# 8stepsV2.net
KiCad netlist of a schematic drawn in EAGLE
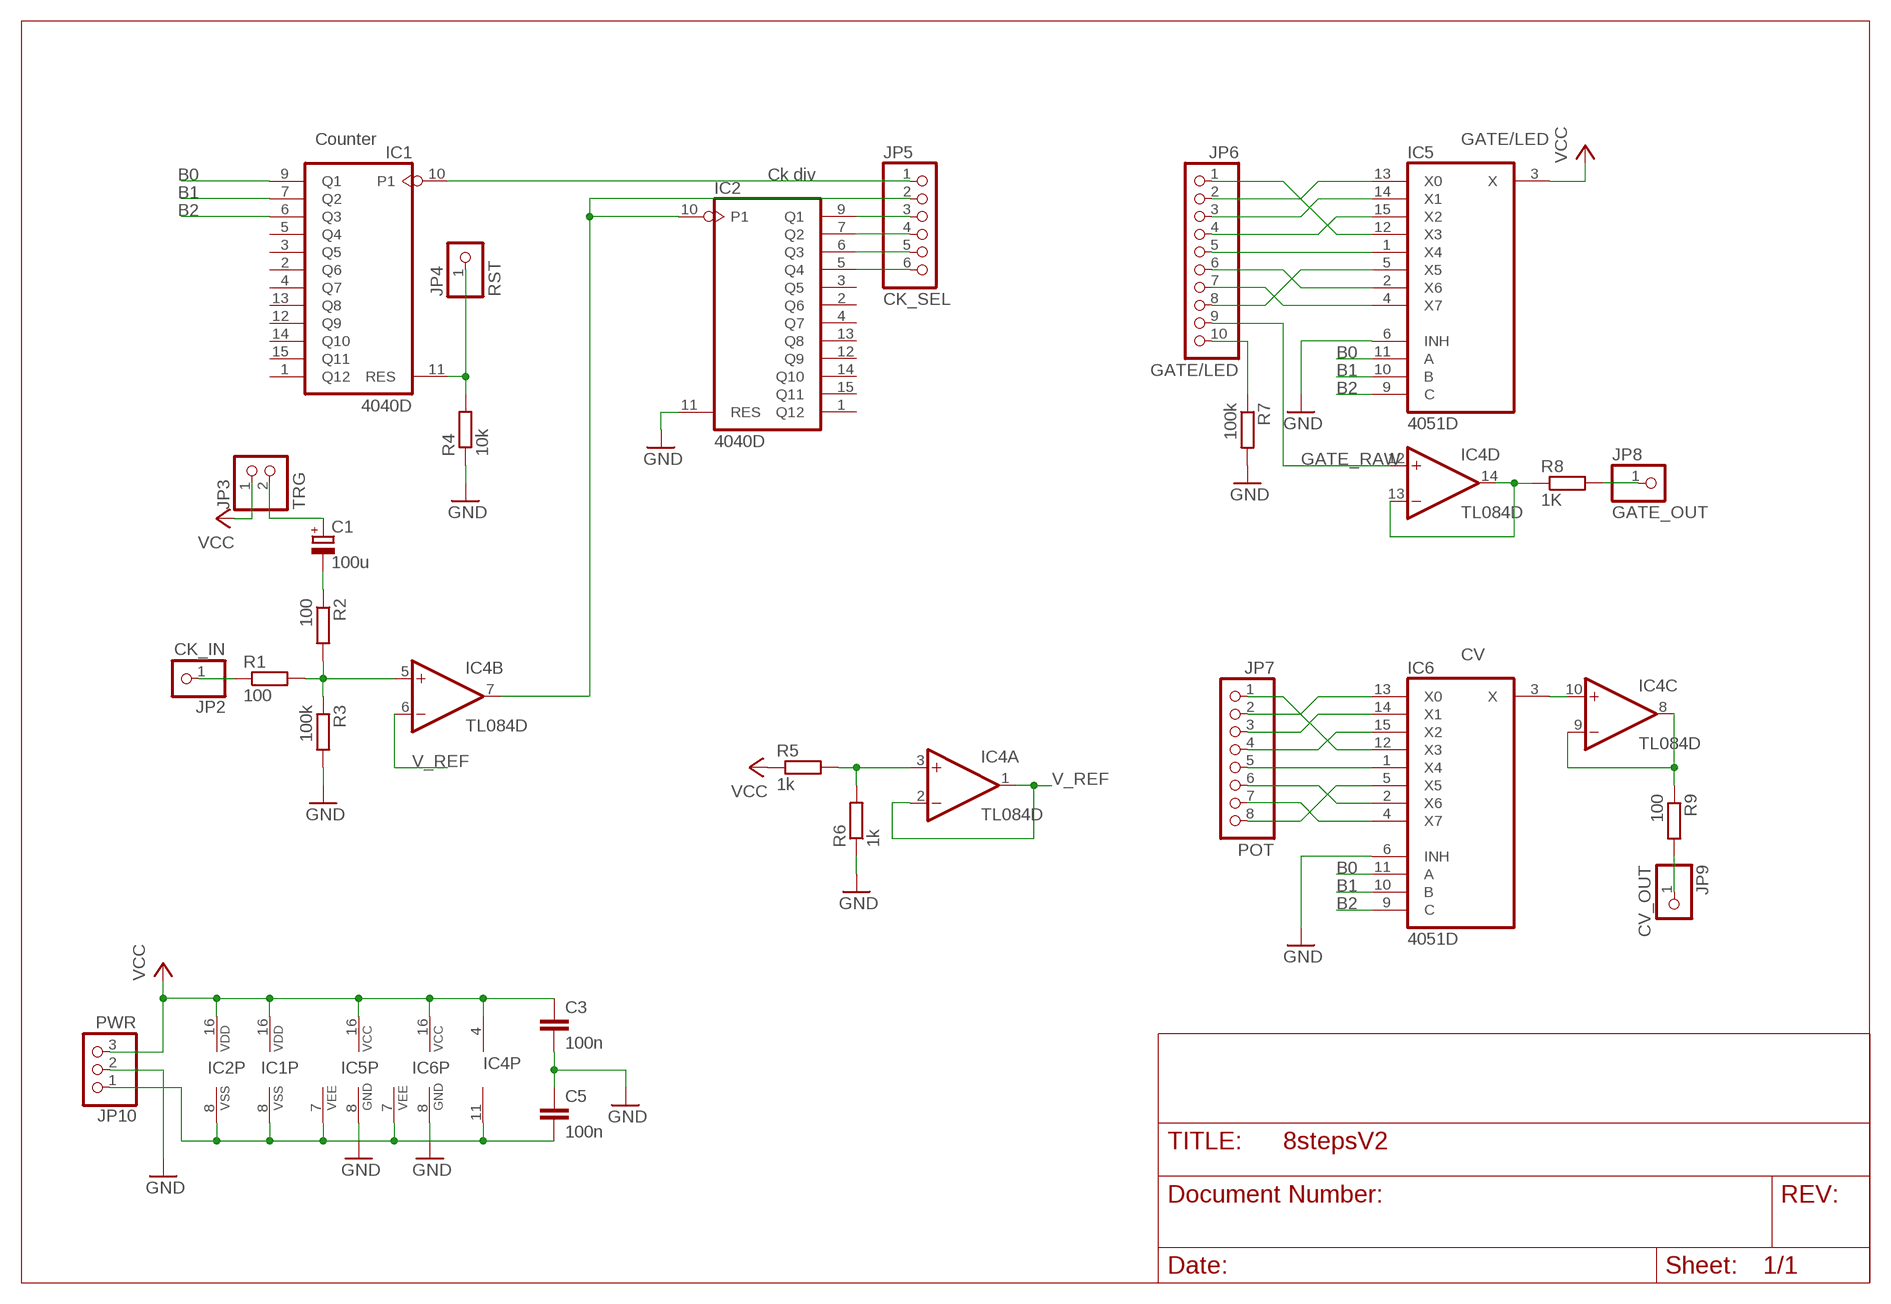
[diagram p0: schematic, sheet 1]

(export (version "E")
  (design (tool "Eeschema 10.0.6"))
  (components
    (comp (ref "C1")
      (value "100u")
      (footprint "eagle-import:E2,5-7")
      (libsource (lib "eagle-import") (part "CPOL-EUE2.5-7"))
    )
    (comp (ref "C3")
      (value "100n")
      (footprint "eagle-import:C025-024X044")
      (libsource (lib "eagle-import") (part "C-EU025-024X044"))
    )
    (comp (ref "C5")
      (value "100n")
      (footprint "eagle-import:C025-024X044")
      (libsource (lib "eagle-import") (part "C-EU025-024X044"))
    )
    (comp (ref "IC1")
      (value "4040D")
      (footprint "eagle-import:SO16")
      (libsource (lib "eagle-import") (part "4040D"))
    )
    (comp (ref "IC2")
      (value "4040D")
      (footprint "eagle-import:SO16")
      (libsource (lib "eagle-import") (part "4040D"))
    )
    (comp (ref "IC4")
      (value "TL084D")
      (footprint "eagle-import:SO14")
      (libsource (lib "eagle-import") (part "TL084D"))
    )
    (comp (ref "IC5")
      (value "4051D")
      (footprint "eagle-import:SO16")
      (libsource (lib "eagle-import") (part "4051D"))
    )
    (comp (ref "IC6")
      (value "4051D")
      (footprint "eagle-import:SO16")
      (libsource (lib "eagle-import") (part "4051D"))
    )
    (comp (ref "JP2")
      (value "CK_IN")
      (footprint "eagle-import:1X01")
      (libsource (lib "eagle-import") (part "PINHD-1X1"))
    )
    (comp (ref "JP3")
      (value "TRG")
      (footprint "eagle-import:1X02")
      (libsource (lib "eagle-import") (part "PINHD-1X2"))
    )
    (comp (ref "JP4")
      (value "RST")
      (footprint "eagle-import:1X01")
      (libsource (lib "eagle-import") (part "PINHD-1X1"))
    )
    (comp (ref "JP5")
      (value "CK_SEL")
      (footprint "eagle-import:1X06")
      (libsource (lib "eagle-import") (part "PINHD-1X6"))
    )
    (comp (ref "JP6")
      (value "GATE/LED")
      (footprint "eagle-import:1X10")
      (libsource (lib "eagle-import") (part "PINHD-1X10"))
    )
    (comp (ref "JP7")
      (value "POT")
      (footprint "eagle-import:1X08")
      (libsource (lib "eagle-import") (part "PINHD-1X8"))
    )
    (comp (ref "JP8")
      (value "GATE_OUT")
      (footprint "eagle-import:1X01")
      (libsource (lib "eagle-import") (part "PINHD-1X1"))
    )
    (comp (ref "JP9")
      (value "CV_OUT")
      (footprint "eagle-import:1X01")
      (libsource (lib "eagle-import") (part "PINHD-1X1"))
    )
    (comp (ref "JP10")
      (value "PWR")
      (footprint "eagle-import:1X03")
      (libsource (lib "eagle-import") (part "PINHD-1X3"))
    )
    (comp (ref "R1")
      (value "100")
      (footprint "eagle-import:R0805")
      (libsource (lib "eagle-import") (part "R-EU_R0805"))
    )
    (comp (ref "R2")
      (value "100")
      (footprint "eagle-import:R0805")
      (libsource (lib "eagle-import") (part "R-EU_R0805"))
    )
    (comp (ref "R3")
      (value "100k")
      (footprint "eagle-import:R0805")
      (libsource (lib "eagle-import") (part "R-EU_R0805"))
    )
    (comp (ref "R4")
      (value "10k")
      (footprint "eagle-import:R0805")
      (libsource (lib "eagle-import") (part "R-EU_R0805"))
    )
    (comp (ref "R5")
      (value "1k")
      (footprint "eagle-import:R0805")
      (libsource (lib "eagle-import") (part "R-EU_R0805"))
    )
    (comp (ref "R6")
      (value "1k")
      (footprint "eagle-import:R0805")
      (libsource (lib "eagle-import") (part "R-EU_R0805"))
    )
    (comp (ref "R7")
      (value "100k")
      (footprint "eagle-import:R0805")
      (libsource (lib "eagle-import") (part "R-EU_R0805"))
    )
    (comp (ref "R8")
      (value "1K")
      (footprint "eagle-import:R0805")
      (libsource (lib "eagle-import") (part "R-EU_R0805"))
    )
    (comp (ref "R9")
      (value "100")
      (footprint "eagle-import:R0805")
      (libsource (lib "eagle-import") (part "R-EU_R0805"))
    )
  )
  (nets
    (net (code "1") (name "/B0") (class "Default")
      (node (ref "IC1") (pin "9") (pinfunction "Q1_9") (pintype "output"))
      (node (ref "IC5") (pin "11") (pinfunction "A_11") (pintype "input"))
      (node (ref "IC6") (pin "11") (pinfunction "A_11") (pintype "input"))
    )
    (net (code "2") (name "/B1") (class "Default")
      (node (ref "IC1") (pin "7") (pinfunction "Q2_7") (pintype "output"))
      (node (ref "IC5") (pin "10") (pinfunction "B_10") (pintype "input"))
      (node (ref "IC6") (pin "10") (pinfunction "B_10") (pintype "input"))
    )
    (net (code "3") (name "/B2") (class "Default")
      (node (ref "IC1") (pin "6") (pinfunction "Q3_6") (pintype "output"))
      (node (ref "IC5") (pin "9") (pinfunction "C_9") (pintype "input"))
      (node (ref "IC6") (pin "9") (pinfunction "C_9") (pintype "input"))
    )
    (net (code "4") (name "/GATE_RAW") (class "Default")
      (node (ref "IC4") (pin "12") (pinfunction "+IN_12") (pintype "input"))
      (node (ref "JP6") (pin "9") (pinfunction "9_9") (pintype "passive"))
    )
    (net (code "5") (name "/V_REF") (class "Default")
      (node (ref "IC4") (pin "1") (pinfunction "OUT_1") (pintype "output"))
      (node (ref "IC4") (pin "2") (pinfunction "-IN_2") (pintype "input"))
      (node (ref "IC4") (pin "6") (pinfunction "-IN_6") (pintype "input"))
    )
    (net (code "6") (name "GND") (class "Default")
      (node (ref "C3") (pin "2") (pinfunction "2_2") (pintype "passive"))
      (node (ref "C5") (pin "1") (pinfunction "1_1") (pintype "passive"))
      (node (ref "IC2") (pin "11") (pinfunction "RES_11") (pintype "input"))
      (node (ref "IC5") (pin "6") (pinfunction "INH_6") (pintype "input"))
      (node (ref "IC5") (pin "8") (pinfunction "GND_8") (pintype "power_in"))
      (node (ref "IC6") (pin "6") (pinfunction "INH_6") (pintype "input"))
      (node (ref "IC6") (pin "8") (pinfunction "GND_8") (pintype "power_in"))
      (node (ref "JP10") (pin "2") (pinfunction "2_2") (pintype "passive"))
      (node (ref "R3") (pin "2") (pinfunction "2_2") (pintype "passive"))
      (node (ref "R4") (pin "1") (pinfunction "1_1") (pintype "passive"))
      (node (ref "R6") (pin "1") (pinfunction "1_1") (pintype "passive"))
      (node (ref "R7") (pin "2") (pinfunction "2_2") (pintype "passive"))
    )
    (net (code "7") (name "Net-(C1-Pad+)") (class "Default")
      (node (ref "C1") (pin "+") (pinfunction "+_+") (pintype "passive"))
      (node (ref "JP3") (pin "2") (pinfunction "2_2") (pintype "passive"))
    )
    (net (code "8") (name "Net-(C1-Pad-)") (class "Default")
      (node (ref "C1") (pin "-") (pinfunction "-_-") (pintype "passive"))
      (node (ref "R2") (pin "1") (pinfunction "1_1") (pintype "passive"))
    )
    (net (code "9") (name "Net-(IC1A-P1)") (class "Default")
      (node (ref "IC1") (pin "10") (pinfunction "P1_10") (pintype "input"))
      (node (ref "JP5") (pin "1") (pinfunction "1_1") (pintype "passive"))
    )
    (net (code "10") (name "Net-(IC1A-RES)") (class "Default")
      (node (ref "IC1") (pin "11") (pinfunction "RES_11") (pintype "input"))
      (node (ref "JP4") (pin "1") (pinfunction "1_1") (pintype "passive"))
      (node (ref "R4") (pin "2") (pinfunction "2_2") (pintype "passive"))
    )
    (net (code "11") (name "Net-(IC1B-VSS)") (class "Default")
      (node (ref "C5") (pin "2") (pinfunction "2_2") (pintype "passive"))
      (node (ref "IC1") (pin "8") (pinfunction "VSS_8") (pintype "power_in"))
      (node (ref "IC2") (pin "8") (pinfunction "VSS_8") (pintype "power_in"))
      (node (ref "IC4") (pin "11") (pinfunction "V-_11") (pintype "power_in"))
      (node (ref "IC5") (pin "7") (pinfunction "VEE_7") (pintype "power_in"))
      (node (ref "IC6") (pin "7") (pinfunction "VEE_7") (pintype "power_in"))
      (node (ref "JP10") (pin "1") (pinfunction "1_1") (pintype "passive"))
    )
    (net (code "12") (name "Net-(IC2A-P1)") (class "Default")
      (node (ref "IC2") (pin "10") (pinfunction "P1_10") (pintype "input"))
      (node (ref "IC4") (pin "7") (pinfunction "OUT_7") (pintype "output"))
      (node (ref "JP5") (pin "2") (pinfunction "2_2") (pintype "passive"))
    )
    (net (code "13") (name "Net-(IC2A-Q1)") (class "Default")
      (node (ref "IC2") (pin "9") (pinfunction "Q1_9") (pintype "output"))
      (node (ref "JP5") (pin "3") (pinfunction "3_3") (pintype "passive"))
    )
    (net (code "14") (name "Net-(IC2A-Q2)") (class "Default")
      (node (ref "IC2") (pin "7") (pinfunction "Q2_7") (pintype "output"))
      (node (ref "JP5") (pin "4") (pinfunction "4_4") (pintype "passive"))
    )
    (net (code "15") (name "Net-(IC2A-Q3)") (class "Default")
      (node (ref "IC2") (pin "6") (pinfunction "Q3_6") (pintype "output"))
      (node (ref "JP5") (pin "5") (pinfunction "5_5") (pintype "passive"))
    )
    (net (code "16") (name "Net-(IC2A-Q4)") (class "Default")
      (node (ref "IC2") (pin "5") (pinfunction "Q4_5") (pintype "output"))
      (node (ref "JP5") (pin "6") (pinfunction "6_6") (pintype "passive"))
    )
    (net (code "17") (name "Net-(IC4A-+IN)") (class "Default")
      (node (ref "IC4") (pin "3") (pinfunction "+IN_3") (pintype "input"))
      (node (ref "R5") (pin "2") (pinfunction "2_2") (pintype "passive"))
      (node (ref "R6") (pin "2") (pinfunction "2_2") (pintype "passive"))
    )
    (net (code "18") (name "Net-(IC4B-+IN)") (class "Default")
      (node (ref "IC4") (pin "5") (pinfunction "+IN_5") (pintype "input"))
      (node (ref "R1") (pin "2") (pinfunction "2_2") (pintype "passive"))
      (node (ref "R2") (pin "2") (pinfunction "2_2") (pintype "passive"))
      (node (ref "R3") (pin "1") (pinfunction "1_1") (pintype "passive"))
    )
    (net (code "19") (name "Net-(IC4C-+IN)") (class "Default")
      (node (ref "IC4") (pin "10") (pinfunction "+IN_10") (pintype "input"))
      (node (ref "IC6") (pin "3") (pinfunction "X_3") (pintype "bidirectional"))
    )
    (net (code "20") (name "Net-(IC4C--IN)") (class "Default")
      (node (ref "IC4") (pin "8") (pinfunction "OUT_8") (pintype "output"))
      (node (ref "IC4") (pin "9") (pinfunction "-IN_9") (pintype "input"))
      (node (ref "R9") (pin "1") (pinfunction "1_1") (pintype "passive"))
    )
    (net (code "21") (name "Net-(IC4D--IN)") (class "Default")
      (node (ref "IC4") (pin "13") (pinfunction "-IN_13") (pintype "input"))
      (node (ref "IC4") (pin "14") (pinfunction "OUT_14") (pintype "output"))
      (node (ref "R8") (pin "1") (pinfunction "1_1") (pintype "passive"))
    )
    (net (code "22") (name "Net-(IC5A-X0)") (class "Default")
      (node (ref "IC5") (pin "13") (pinfunction "X0_13") (pintype "bidirectional"))
      (node (ref "JP6") (pin "2") (pinfunction "2_2") (pintype "passive"))
    )
    (net (code "23") (name "Net-(IC5A-X1)") (class "Default")
      (node (ref "IC5") (pin "14") (pinfunction "X1_14") (pintype "bidirectional"))
      (node (ref "JP6") (pin "3") (pinfunction "3_3") (pintype "passive"))
    )
    (net (code "24") (name "Net-(IC5A-X2)") (class "Default")
      (node (ref "IC5") (pin "15") (pinfunction "X2_15") (pintype "bidirectional"))
      (node (ref "JP6") (pin "4") (pinfunction "4_4") (pintype "passive"))
    )
    (net (code "25") (name "Net-(IC5A-X3)") (class "Default")
      (node (ref "IC5") (pin "12") (pinfunction "X3_12") (pintype "bidirectional"))
      (node (ref "JP6") (pin "1") (pinfunction "1_1") (pintype "passive"))
    )
    (net (code "26") (name "Net-(IC5A-X4)") (class "Default")
      (node (ref "IC5") (pin "1") (pinfunction "X4_1") (pintype "bidirectional"))
      (node (ref "JP6") (pin "5") (pinfunction "5_5") (pintype "passive"))
    )
    (net (code "27") (name "Net-(IC5A-X5)") (class "Default")
      (node (ref "IC5") (pin "5") (pinfunction "X5_5") (pintype "bidirectional"))
      (node (ref "JP6") (pin "8") (pinfunction "8_8") (pintype "passive"))
    )
    (net (code "28") (name "Net-(IC5A-X6)") (class "Default")
      (node (ref "IC5") (pin "2") (pinfunction "X6_2") (pintype "bidirectional"))
      (node (ref "JP6") (pin "6") (pinfunction "6_6") (pintype "passive"))
    )
    (net (code "29") (name "Net-(IC5A-X7)") (class "Default")
      (node (ref "IC5") (pin "4") (pinfunction "X7_4") (pintype "bidirectional"))
      (node (ref "JP6") (pin "7") (pinfunction "7_7") (pintype "passive"))
    )
    (net (code "30") (name "Net-(IC6A-X0)") (class "Default")
      (node (ref "IC6") (pin "13") (pinfunction "X0_13") (pintype "bidirectional"))
      (node (ref "JP7") (pin "2") (pinfunction "2_2") (pintype "passive"))
    )
    (net (code "31") (name "Net-(IC6A-X1)") (class "Default")
      (node (ref "IC6") (pin "14") (pinfunction "X1_14") (pintype "bidirectional"))
      (node (ref "JP7") (pin "3") (pinfunction "3_3") (pintype "passive"))
    )
    (net (code "32") (name "Net-(IC6A-X2)") (class "Default")
      (node (ref "IC6") (pin "15") (pinfunction "X2_15") (pintype "bidirectional"))
      (node (ref "JP7") (pin "4") (pinfunction "4_4") (pintype "passive"))
    )
    (net (code "33") (name "Net-(IC6A-X3)") (class "Default")
      (node (ref "IC6") (pin "12") (pinfunction "X3_12") (pintype "bidirectional"))
      (node (ref "JP7") (pin "1") (pinfunction "1_1") (pintype "passive"))
    )
    (net (code "34") (name "Net-(IC6A-X4)") (class "Default")
      (node (ref "IC6") (pin "1") (pinfunction "X4_1") (pintype "bidirectional"))
      (node (ref "JP7") (pin "5") (pinfunction "5_5") (pintype "passive"))
    )
    (net (code "35") (name "Net-(IC6A-X5)") (class "Default")
      (node (ref "IC6") (pin "5") (pinfunction "X5_5") (pintype "bidirectional"))
      (node (ref "JP7") (pin "8") (pinfunction "8_8") (pintype "passive"))
    )
    (net (code "36") (name "Net-(IC6A-X6)") (class "Default")
      (node (ref "IC6") (pin "2") (pinfunction "X6_2") (pintype "bidirectional"))
      (node (ref "JP7") (pin "6") (pinfunction "6_6") (pintype "passive"))
    )
    (net (code "37") (name "Net-(IC6A-X7)") (class "Default")
      (node (ref "IC6") (pin "4") (pinfunction "X7_4") (pintype "bidirectional"))
      (node (ref "JP7") (pin "7") (pinfunction "7_7") (pintype "passive"))
    )
    (net (code "38") (name "Net-(JP2-Pad1)") (class "Default")
      (node (ref "JP2") (pin "1") (pinfunction "1_1") (pintype "passive"))
      (node (ref "R1") (pin "1") (pinfunction "1_1") (pintype "passive"))
    )
    (net (code "39") (name "Net-(JP6-Pad10)") (class "Default")
      (node (ref "JP6") (pin "10") (pinfunction "10_10") (pintype "passive"))
      (node (ref "R7") (pin "1") (pinfunction "1_1") (pintype "passive"))
    )
    (net (code "40") (name "Net-(JP8-Pad1)") (class "Default")
      (node (ref "JP8") (pin "1") (pinfunction "1_1") (pintype "passive"))
      (node (ref "R8") (pin "2") (pinfunction "2_2") (pintype "passive"))
    )
    (net (code "41") (name "Net-(JP9-Pad1)") (class "Default")
      (node (ref "JP9") (pin "1") (pinfunction "1_1") (pintype "passive"))
      (node (ref "R9") (pin "2") (pinfunction "2_2") (pintype "passive"))
    )
    (net (code "42") (name "VCC") (class "Default")
      (node (ref "C3") (pin "1") (pinfunction "1_1") (pintype "passive"))
      (node (ref "IC1") (pin "16") (pinfunction "VDD_16") (pintype "power_in"))
      (node (ref "IC2") (pin "16") (pinfunction "VDD_16") (pintype "power_in"))
      (node (ref "IC4") (pin "4") (pinfunction "V+_4") (pintype "power_in"))
      (node (ref "IC5") (pin "16") (pinfunction "VCC_16") (pintype "power_in"))
      (node (ref "IC5") (pin "3") (pinfunction "X_3") (pintype "bidirectional"))
      (node (ref "IC6") (pin "16") (pinfunction "VCC_16") (pintype "power_in"))
      (node (ref "JP10") (pin "3") (pinfunction "3_3") (pintype "passive"))
      (node (ref "JP3") (pin "1") (pinfunction "1_1") (pintype "passive"))
      (node (ref "R5") (pin "1") (pinfunction "1_1") (pintype "passive"))
    )
    (net (code "43") (name "unconnected-(IC1A-Q4-Pad5)") (class "Default")
      (node (ref "IC1") (pin "5") (pinfunction "Q4_5") (pintype "output"))
    )
    (net (code "44") (name "unconnected-(IC1A-Q5-Pad3)") (class "Default")
      (node (ref "IC1") (pin "3") (pinfunction "Q5_3") (pintype "output"))
    )
    (net (code "45") (name "unconnected-(IC1A-Q6-Pad2)") (class "Default")
      (node (ref "IC1") (pin "2") (pinfunction "Q6_2") (pintype "output"))
    )
    (net (code "46") (name "unconnected-(IC1A-Q7-Pad4)") (class "Default")
      (node (ref "IC1") (pin "4") (pinfunction "Q7_4") (pintype "output"))
    )
    (net (code "47") (name "unconnected-(IC1A-Q8-Pad13)") (class "Default")
      (node (ref "IC1") (pin "13") (pinfunction "Q8_13") (pintype "output"))
    )
    (net (code "48") (name "unconnected-(IC1A-Q9-Pad12)") (class "Default")
      (node (ref "IC1") (pin "12") (pinfunction "Q9_12") (pintype "output"))
    )
    (net (code "49") (name "unconnected-(IC1A-Q10-Pad14)") (class "Default")
      (node (ref "IC1") (pin "14") (pinfunction "Q10_14") (pintype "output"))
    )
    (net (code "50") (name "unconnected-(IC1A-Q11-Pad15)") (class "Default")
      (node (ref "IC1") (pin "15") (pinfunction "Q11_15") (pintype "output"))
    )
    (net (code "51") (name "unconnected-(IC1A-Q12-Pad1)") (class "Default")
      (node (ref "IC1") (pin "1") (pinfunction "Q12_1") (pintype "output"))
    )
    (net (code "52") (name "unconnected-(IC2A-Q5-Pad3)") (class "Default")
      (node (ref "IC2") (pin "3") (pinfunction "Q5_3") (pintype "output"))
    )
    (net (code "53") (name "unconnected-(IC2A-Q6-Pad2)") (class "Default")
      (node (ref "IC2") (pin "2") (pinfunction "Q6_2") (pintype "output"))
    )
    (net (code "54") (name "unconnected-(IC2A-Q7-Pad4)") (class "Default")
      (node (ref "IC2") (pin "4") (pinfunction "Q7_4") (pintype "output"))
    )
    (net (code "55") (name "unconnected-(IC2A-Q8-Pad13)") (class "Default")
      (node (ref "IC2") (pin "13") (pinfunction "Q8_13") (pintype "output"))
    )
    (net (code "56") (name "unconnected-(IC2A-Q9-Pad12)") (class "Default")
      (node (ref "IC2") (pin "12") (pinfunction "Q9_12") (pintype "output"))
    )
    (net (code "57") (name "unconnected-(IC2A-Q10-Pad14)") (class "Default")
      (node (ref "IC2") (pin "14") (pinfunction "Q10_14") (pintype "output"))
    )
    (net (code "58") (name "unconnected-(IC2A-Q11-Pad15)") (class "Default")
      (node (ref "IC2") (pin "15") (pinfunction "Q11_15") (pintype "output"))
    )
    (net (code "59") (name "unconnected-(IC2A-Q12-Pad1)") (class "Default")
      (node (ref "IC2") (pin "1") (pinfunction "Q12_1") (pintype "output"))
    )
  )
)
